# Microphone-Boards_V1_0_MP34DT05TR.net
KiCad netlist of a schematic drawn in Altium Designer
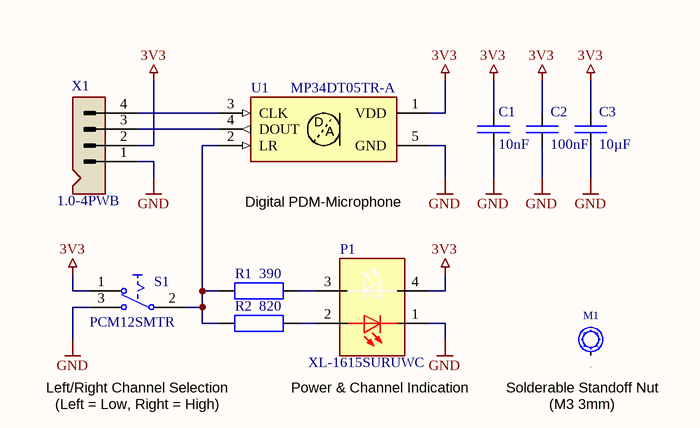
[diagram p0: Microphone-Boards_V1.0_MP34DT05TR.SchDoc]

(export (version "E")
  (design (tool "Eeschema 10.0.6"))
  (components
    (comp (ref "C1")
      (value "10nF")
      (footprint "SMD Keramikkondensator 0603")
      (description "CAP-MK")
      (libsource (lib "AudioAmp") (part "C-CAPACITOR"))
    )
    (comp (ref "C2")
      (value "100nF")
      (footprint "SMD Keramikkondensator 0603")
      (description "SMD Ceramic Capacitor E6")
      (libsource (lib "Ceramic Capacitors-E6") (part "E6 - 100nF"))
    )
    (comp (ref "C3")
      (value "10µF")
      (footprint "SMD Keramikkondensator 1206")
      (description "SMD Ceramic Capacitor E6")
      (libsource (lib "Ceramic Capacitors-E6") (part "E6 - 10uF"))
    )
    (comp (ref "M1")
      (value "SMTSO-M3-3ET")
      (footprint "SMD Solder-Nut (M3 3mm)")
      (description "Solderable Standoff Nut")
      (libsource (lib "Velotour_2022") (part "M-Spacer_M3_3mm"))
    )
    (comp (ref "P1")
      (value "XL-1615SURUWC")
      (footprint "SMD LED 0606")
      (description "LED Red/White")
      (libsource (lib "Microphone-Boards") (part "P-XL-1615SURUWC"))
    )
    (comp (ref "R1")
      (value "390")
      (footprint "SMD Widerstand 0603")
      (description "SMD-Widerstand 1/4W")
      (libsource (lib "Backplane_1") (part "R-RESISTOR"))
    )
    (comp (ref "R2")
      (value "820")
      (footprint "SMD Widerstand 0603")
      (description "SMD-Widerstand 1/4W")
      (libsource (lib "Backplane_1") (part "R-RESISTOR"))
    )
    (comp (ref "S1")
      (value "PCM12SMTR")
      (footprint "SMD Switch SPDT (PCM12SMTR)")
      (description "Miniature Slide Switch")
      (libsource (lib "Custom ST-Link") (part "S-PCM12SMTR"))
    )
    (comp (ref "U1")
      (value "MP34DT05TR-A")
      (footprint "SMD Microphone (MP34DT05TR-A)")
      (description "Digital PDM MEMS Microphone (Top Port)")
      (libsource (lib "Microphone-Boards") (part "U-MP34DT05TR-A"))
    )
    (comp (ref "X1")
      (value "1.0-4PWB")
      (footprint "SMD Connector (SM04B-SRSS-TB)")
      (description "Wire To Board Connector (1x4P 1.0mm)")
      (libsource (lib "Audio-Beamformer") (part "X-Stiftleiste (4-Fach)"))
    )
  )
  (nets
    (net (code "1") (name "/M") (class "Default")
      (node (ref "M1") (pin "1") (pinfunction "1_1") (pintype "passive"))
    )
    (net (code "2") (name "3V3") (class "Default")
      (node (ref "C1") (pin "2") (pinfunction "2_2") (pintype "passive"))
      (node (ref "C2") (pin "2") (pinfunction "2_2") (pintype "passive"))
      (node (ref "C3") (pin "2") (pinfunction "2_2") (pintype "passive"))
      (node (ref "P1") (pin "4") (pinfunction "WA_4") (pintype "passive"))
      (node (ref "S1") (pin "1") (pinfunction "NC1_1") (pintype "passive"))
      (node (ref "U1") (pin "1") (pinfunction "VDD_1") (pintype "power_in"))
      (node (ref "X1") (pin "2") (pinfunction "2_2") (pintype "passive"))
    )
    (net (code "3") (name "GND") (class "Default")
      (node (ref "C1") (pin "1") (pinfunction "1_1") (pintype "passive"))
      (node (ref "C2") (pin "1") (pinfunction "1_1") (pintype "passive"))
      (node (ref "C3") (pin "1") (pinfunction "1_1") (pintype "passive"))
      (node (ref "P1") (pin "1") (pinfunction "RC_1") (pintype "passive"))
      (node (ref "S1") (pin "3") (pinfunction "NO1_3") (pintype "passive"))
      (node (ref "U1") (pin "5") (pinfunction "GND_5") (pintype "power_in"))
      (node (ref "X1") (pin "1") (pinfunction "1_1") (pintype "passive"))
    )
    (net (code "4") (name "Net-(P1-RA)") (class "Default")
      (node (ref "P1") (pin "2") (pinfunction "RA_2") (pintype "passive"))
      (node (ref "R2") (pin "2") (pinfunction "2_2") (pintype "passive"))
    )
    (net (code "5") (name "Net-(P1-WC)") (class "Default")
      (node (ref "P1") (pin "3") (pinfunction "WC_3") (pintype "passive"))
      (node (ref "R1") (pin "2") (pinfunction "2_2") (pintype "passive"))
    )
    (net (code "6") (name "Net-(S1-COMMON1)") (class "Default")
      (node (ref "R1") (pin "1") (pinfunction "1_1") (pintype "passive"))
      (node (ref "R2") (pin "1") (pinfunction "1_1") (pintype "passive"))
      (node (ref "S1") (pin "2") (pinfunction "COMMON1_2") (pintype "passive"))
      (node (ref "U1") (pin "2") (pinfunction "LR_2") (pintype "input"))
    )
    (net (code "7") (name "Net-(U1-CLK)") (class "Default")
      (node (ref "U1") (pin "3") (pinfunction "CLK_3") (pintype "input"))
      (node (ref "X1") (pin "4") (pinfunction "4_4") (pintype "passive"))
    )
    (net (code "8") (name "Net-(U1-DOUT)") (class "Default")
      (node (ref "U1") (pin "4") (pinfunction "DOUT_4") (pintype "output"))
      (node (ref "X1") (pin "3") (pinfunction "3_3") (pintype "passive"))
    )
  )
)
